# POWER.net
KiCad netlist of a schematic drawn in Altium Designer
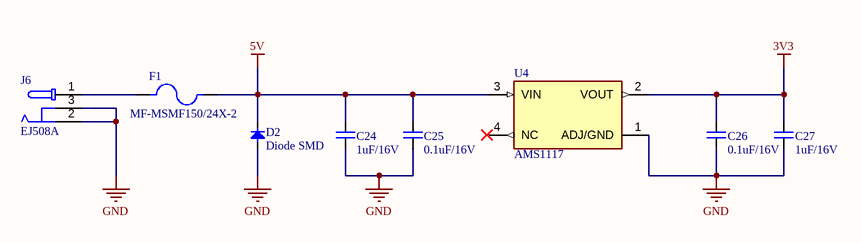
[diagram p0: POWER.SchDoc]

(export (version "E")
  (design (tool "Eeschema 10.0.6"))
  (components
    (comp (ref "C24")
      (value "1uF/16V")
      (footprint "CAP_C_1608X80")
      (description "CAP_Chip")
      (libsource (lib "BTL_SCHLIB") (part "CAP_SMD"))
    )
    (comp (ref "C25")
      (value "0.1uF/16V")
      (footprint "CAP_C_1608X80")
      (description "CAP_Chip")
      (libsource (lib "BTL_SCHLIB") (part "CAP_SMD"))
    )
    (comp (ref "C26")
      (value "0.1uF/16V")
      (footprint "CAP_C_1608X80")
      (description "CAP_Chip")
      (libsource (lib "BTL_SCHLIB") (part "CAP_SMD"))
    )
    (comp (ref "C27")
      (value "1uF/16V")
      (footprint "CAP_C_1608X80")
      (description "CAP_Chip")
      (libsource (lib "BTL_SCHLIB") (part "CAP_SMD"))
    )
    (comp (ref "D2")
      (value "Diode SMD")
      (footprint "DO-214AC_SMA")
      (description "Default Diode")
      (fields (field (name "PUBLISHER") "Altium Limited"))
      (libsource (lib "BTL_SCHLIB") (part "Diode SMD"))
    )
    (comp (ref "F1")
      (value "MF-MSMF150/24X-2")
      (footprint "FUSER_MF-MSMF150/24X-2")
      (description "Polymeric PTC Resettable Fuse 24V 1.5 A Ih Surface Mount 1812 (4532 Metric), Concave")
      (fields (field (name "DIGI-KEY_PART_NUMBER") "MF-MSMF150/24X-2TR-ND") (field (name "MF") "Bourns"))
      (libsource (lib "BTL_SCHLIB") (part "MF-MSMF150/24X-2"))
    )
    (comp (ref "J6")
      (value "EJ508A")
      (footprint "MPD_EJ508A")
      (description "Power Barrel Connector Jack 2.10mm ID _0.083_, 5.50mm OD _0.217_ Through Hole, Right Angle")
      (fields (field (name "MF") "MPD"))
      (libsource (lib "BTL_SCHLIB") (part "EJ508A"))
    )
    (comp (ref "U4")
      (value "AMS1117")
      (footprint "SOT229P700X180-4N")
      (description "1A LOW DROPOUT VOLTAGE REGULATOR SOT-223")
      (fields (field (name "MF") "Advanced Monolithic Systems"))
      (libsource (lib "BTL_SCHLIB") (part "AMS1117"))
    )
  )
  (nets
    (net (code "1") (name "3V3") (class "Default")
      (node (ref "C26") (pin "2") (pinfunction "2_2") (pintype "passive"))
      (node (ref "C27") (pin "2") (pinfunction "2_2") (pintype "passive"))
      (node (ref "U4") (pin "2") (pinfunction "VOUT_2") (pintype "output"))
    )
    (net (code "2") (name "5V") (class "Default")
      (node (ref "C24") (pin "2") (pinfunction "2_2") (pintype "passive"))
      (node (ref "C25") (pin "2") (pinfunction "2_2") (pintype "passive"))
      (node (ref "D2") (pin "1") (pinfunction "K_1") (pintype "passive"))
      (node (ref "F1") (pin "2") (pinfunction "2_2") (pintype "passive"))
      (node (ref "U4") (pin "3") (pinfunction "VIN_3") (pintype "input"))
    )
    (net (code "3") (name "GND") (class "Default")
      (node (ref "C24") (pin "1") (pinfunction "1_1") (pintype "passive"))
      (node (ref "C25") (pin "1") (pinfunction "1_1") (pintype "passive"))
      (node (ref "C26") (pin "1") (pinfunction "1_1") (pintype "passive"))
      (node (ref "C27") (pin "1") (pinfunction "1_1") (pintype "passive"))
      (node (ref "D2") (pin "2") (pinfunction "A_2") (pintype "passive"))
      (node (ref "J6") (pin "2") (pinfunction "2_2") (pintype "passive"))
      (node (ref "J6") (pin "3") (pinfunction "3_3") (pintype "passive"))
      (node (ref "U4") (pin "1") (pinfunction "ADJ/GND_1") (pintype "power_in"))
    )
    (net (code "4") (name "Net-(F1-Pad1)") (class "Default")
      (node (ref "F1") (pin "1") (pinfunction "1_1") (pintype "passive"))
      (node (ref "J6") (pin "1") (pinfunction "1_1") (pintype "passive"))
    )
    (net (code "5") (name "unconnected-(U4-NC-Pad4)") (class "Default")
      (node (ref "U4") (pin "4") (pinfunction "NC_4") (pintype "output+no_connect"))
    )
  )
)
